# Fuel_gauge.net
KiCad netlist of a schematic drawn in Altium Designer
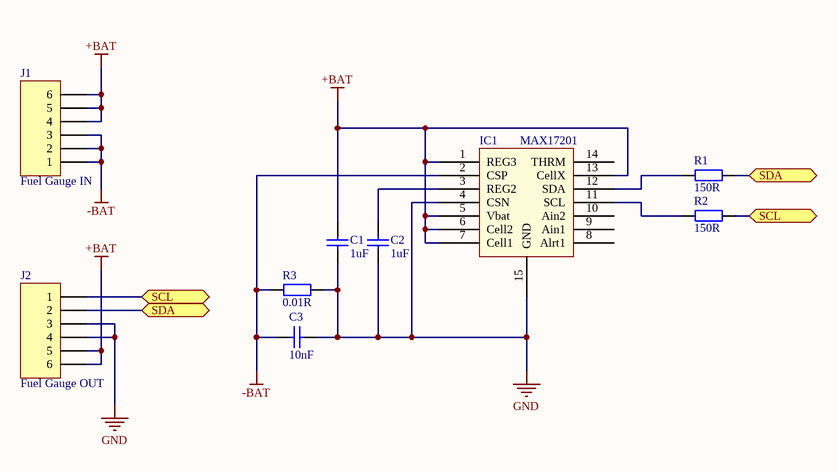
[diagram p0: Fuel gauge.SchDoc]

(export (version "E")
  (design (tool "Eeschema 10.0.6"))
  (components
    (comp (ref "C1")
      (value "Capacitor NP")
      (footprint "0603 cap")
      (fields (field (name "VALVE") "1uF"))
      (libsource (lib "IKSOR_LIB_main") (part "Capacitor NP"))
    )
    (comp (ref "C2")
      (value "Capacitor NP")
      (footprint "0603 cap")
      (fields (field (name "VALVE") "1uF"))
      (libsource (lib "IKSOR_LIB_main") (part "Capacitor NP"))
    )
    (comp (ref "C3")
      (value "Capacitor NP")
      (footprint "0603 cap")
      (fields (field (name "VALVE") "10nF"))
      (libsource (lib "IKSOR_LIB_main") (part "Capacitor NP"))
    )
    (comp (ref "IC1")
      (value "MAX17201")
      (footprint "TDFN14")
      (description "Single cell fuel gauge")
      (libsource (lib "IKSOR_LIB_main") (part "MAX17201"))
    )
    (comp (ref "J1")
      (value "Fuel Gauge IN")
      (footprint "HDR1X6")
      (description "Header, 6-Pin")
      (fields (field (name "PUBLISHER") "Altium Limited"))
      (libsource (lib "Miscellaneous Connectors") (part "Header 6"))
    )
    (comp (ref "J2")
      (value "Fuel Gauge OUT")
      (footprint "HDR1X6")
      (description "Header, 6-Pin")
      (fields (field (name "PUBLISHER") "Altium Limited"))
      (libsource (lib "") (part "Header 6_1"))
    )
    (comp (ref "R1")
      (value "Resistor generic")
      (footprint "0603 RES")
      (description "Resistor SMD")
      (fields (field (name "VALVE") "150R"))
      (libsource (lib "IKSOR_LIB_main") (part "Resistor"))
    )
    (comp (ref "R2")
      (value "Resistor generic")
      (footprint "0603 RES")
      (description "Resistor SMD")
      (fields (field (name "VALVE") "150R"))
      (libsource (lib "IKSOR_LIB_main") (part "Resistor"))
    )
    (comp (ref "R3")
      (value "Resistor generic")
      (footprint "2512 RES")
      (description "Resistor SMD")
      (fields (field (name "VALVE") "0.01R"))
      (libsource (lib "IKSOR_LIB_main") (part "Resistor"))
    )
  )
  (nets
    (net (code "1") (name "+BAT") (class "Default")
      (node (ref "C1") (pin "2") (pinfunction "2_2") (pintype "passive"))
      (node (ref "IC1") (pin "1") (pinfunction "REG3_1") (pintype "passive"))
      (node (ref "IC1") (pin "13") (pinfunction "CellX_13") (pintype "passive"))
      (node (ref "IC1") (pin "5") (pinfunction "Vbat_5") (pintype "passive"))
      (node (ref "IC1") (pin "6") (pinfunction "Cell2_6") (pintype "passive"))
      (node (ref "IC1") (pin "7") (pinfunction "Cell1_7") (pintype "passive"))
      (node (ref "J1") (pin "4") (pinfunction "4_4") (pintype "passive"))
      (node (ref "J1") (pin "5") (pinfunction "5_5") (pintype "passive"))
      (node (ref "J1") (pin "6") (pinfunction "6_6") (pintype "passive"))
      (node (ref "J2") (pin "5") (pinfunction "5_5") (pintype "passive"))
      (node (ref "J2") (pin "6") (pinfunction "6_6") (pintype "passive"))
    )
    (net (code "2") (name "-BAT") (class "Default")
      (node (ref "C3") (pin "2") (pinfunction "2_2") (pintype "passive"))
      (node (ref "IC1") (pin "2") (pinfunction "CSP_2") (pintype "passive"))
      (node (ref "J1") (pin "1") (pinfunction "1_1") (pintype "passive"))
      (node (ref "J1") (pin "2") (pinfunction "2_2") (pintype "passive"))
      (node (ref "J1") (pin "3") (pinfunction "3_3") (pintype "passive"))
      (node (ref "R3") (pin "1") (pinfunction "1_1") (pintype "passive"))
    )
    (net (code "3") (name "/SCL") (class "Default")
      (node (ref "J2") (pin "1") (pinfunction "1_1") (pintype "passive"))
      (node (ref "R2") (pin "2") (pinfunction "2_2") (pintype "passive"))
    )
    (net (code "4") (name "/SDA") (class "Default")
      (node (ref "J2") (pin "2") (pinfunction "2_2") (pintype "passive"))
      (node (ref "R1") (pin "2") (pinfunction "2_2") (pintype "passive"))
    )
    (net (code "5") (name "GND") (class "Default")
      (node (ref "C1") (pin "1") (pinfunction "1_1") (pintype "passive"))
      (node (ref "C2") (pin "1") (pinfunction "1_1") (pintype "passive"))
      (node (ref "C3") (pin "1") (pinfunction "1_1") (pintype "passive"))
      (node (ref "IC1") (pin "15") (pinfunction "GND_15") (pintype "passive"))
      (node (ref "IC1") (pin "4") (pinfunction "CSN_4") (pintype "passive"))
      (node (ref "J2") (pin "3") (pinfunction "3_3") (pintype "passive"))
      (node (ref "J2") (pin "4") (pinfunction "4_4") (pintype "passive"))
      (node (ref "R3") (pin "2") (pinfunction "2_2") (pintype "passive"))
    )
    (net (code "6") (name "Net-(IC1-REG2)") (class "Default")
      (node (ref "C2") (pin "2") (pinfunction "2_2") (pintype "passive"))
      (node (ref "IC1") (pin "3") (pinfunction "REG2_3") (pintype "passive"))
    )
    (net (code "7") (name "Net-(IC1-SCL)") (class "Default")
      (node (ref "IC1") (pin "11") (pinfunction "SCL_11") (pintype "passive"))
      (node (ref "R2") (pin "1") (pinfunction "1_1") (pintype "passive"))
    )
    (net (code "8") (name "Net-(IC1-SDA)") (class "Default")
      (node (ref "IC1") (pin "12") (pinfunction "SDA_12") (pintype "passive"))
      (node (ref "R1") (pin "1") (pinfunction "1_1") (pintype "passive"))
    )
    (net (code "9") (name "unconnected-(IC1-Ain1-Pad9)") (class "Default")
      (node (ref "IC1") (pin "9") (pinfunction "Ain1_9") (pintype "passive"))
    )
    (net (code "10") (name "unconnected-(IC1-Ain2-Pad10)") (class "Default")
      (node (ref "IC1") (pin "10") (pinfunction "Ain2_10") (pintype "passive"))
    )
    (net (code "11") (name "unconnected-(IC1-Alrt1-Pad8)") (class "Default")
      (node (ref "IC1") (pin "8") (pinfunction "Alrt1_8") (pintype "passive"))
    )
    (net (code "12") (name "unconnected-(IC1-THRM-Pad14)") (class "Default")
      (node (ref "IC1") (pin "14") (pinfunction "THRM_14") (pintype "passive"))
    )
  )
)
